# DIOT_EEM_Adapter.net
KiCad netlist of a schematic drawn in Altium Designer
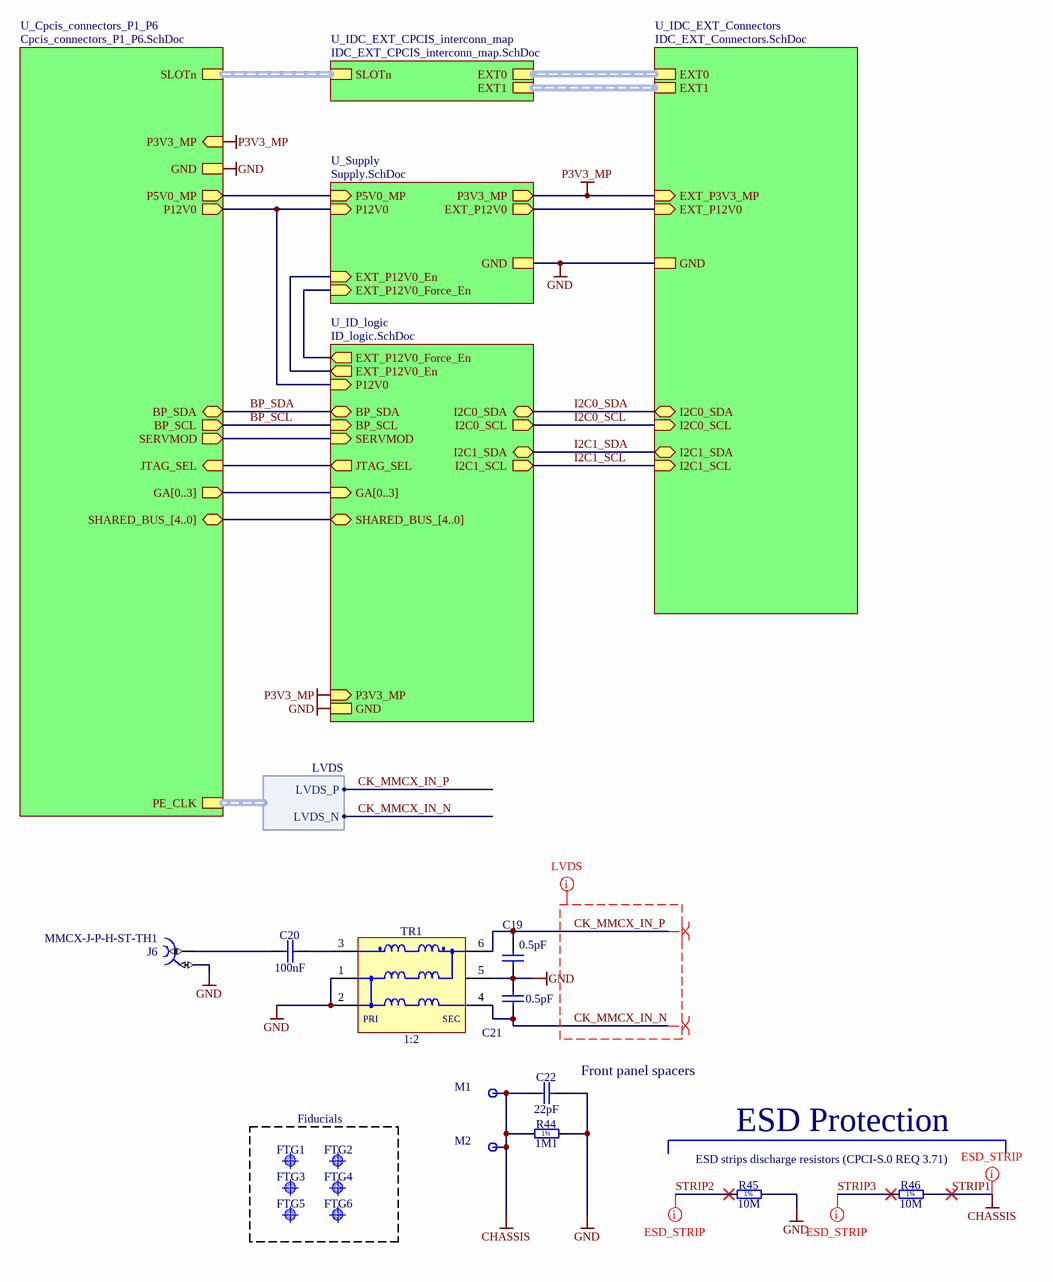
[diagram p0: DIOT_EEM_Adapter.SchDoc]

(export (version "E")
  (design (tool "Eeschema 10.0.6"))
  (components
    (comp (ref "C19")
      (value "0.5pF")
      (footprint "CAPC1005X50N")
      (description "Non-polarised capacitor")
      (fields
        (field (name "PART NUMBER") "CC0402_0.5PF_25V_0.05PF_AVX_04023J0R5ABSTR")
        (field (name "VOLTAGE") "25V")
        (field (name "AUTHOR") "CERN DEM JLC")
      )
      (libsource (lib "Capacitors") (part "Capacitor - non polarized"))
    )
    (comp (ref "C20")
      (value "100nF")
      (footprint "CAPC1005X55N")
      (description "Non-polarised capacitor")
      (fields
        (field (name "PART NUMBER") "CC0402_100NF_16V_10%_X7R")
        (field (name "VOLTAGE") "16V")
        (field (name "AUTHOR") "CERN DEM JLC")
      )
      (libsource (lib "Capacitors") (part "Capacitor - non polarized"))
    )
    (comp (ref "C21")
      (value "0.5pF")
      (footprint "CAPC1005X50N")
      (description "Non-polarised capacitor")
      (fields
        (field (name "PART NUMBER") "CC0402_0.5PF_25V_0.05PF_AVX_04023J0R5ABSTR")
        (field (name "VOLTAGE") "25V")
        (field (name "AUTHOR") "CERN DEM JLC")
      )
      (libsource (lib "Capacitors") (part "Capacitor - non polarized"))
    )
    (comp (ref "C22")
      (value "22pF")
      (footprint "CAPC1005X55N")
      (description "Non-polarised capacitor")
      (fields
        (field (name "PART NUMBER") "CC0402_22PF_50V_5%_C0G")
        (field (name "VOLTAGE") "50V")
        (field (name "AUTHOR") "CERN DEM JLC")
      )
      (libsource (lib "Capacitors") (part "Capacitor - non polarized"))
    )
    (comp (ref "FTG1")
      (value "Use only in PCB")
      (footprint "FIDUCIAL_TOP_S100-200")
      (description "Fiducial Target")
      (fields (field (name "PART NUMBER") "FIDUCIAL_TARGET_S100-200") (field (name "AUTHOR") "CERN DEM JLC"))
      (libsource (lib "Eletro-mechanical") (part "Fiducial Target"))
    )
    (comp (ref "FTG2")
      (value "Use only in PCB")
      (footprint "FIDUCIAL_TOP_S100-200")
      (description "Fiducial Target")
      (fields (field (name "PART NUMBER") "FIDUCIAL_TARGET_S100-200") (field (name "AUTHOR") "CERN DEM JLC"))
      (libsource (lib "Eletro-mechanical") (part "Fiducial Target"))
    )
    (comp (ref "FTG3")
      (value "Use only in PCB")
      (footprint "FIDUCIAL_TOP_S100-200")
      (description "Fiducial Target")
      (fields (field (name "PART NUMBER") "FIDUCIAL_TARGET_S100-200") (field (name "AUTHOR") "CERN DEM JLC"))
      (libsource (lib "Eletro-mechanical") (part "Fiducial Target"))
    )
    (comp (ref "FTG4")
      (value "Use only in PCB")
      (footprint "FIDUCIAL_TOP_S100-200")
      (description "Fiducial Target")
      (fields (field (name "PART NUMBER") "FIDUCIAL_TARGET_S100-200") (field (name "AUTHOR") "CERN DEM JLC"))
      (libsource (lib "Eletro-mechanical") (part "Fiducial Target"))
    )
    (comp (ref "FTG5")
      (value "Use only in PCB")
      (footprint "FIDUCIAL_TOP_S100-200")
      (description "Fiducial Target")
      (fields (field (name "PART NUMBER") "FIDUCIAL_TARGET_S100-200") (field (name "AUTHOR") "CERN DEM JLC"))
      (libsource (lib "Eletro-mechanical") (part "Fiducial Target"))
    )
    (comp (ref "FTG6")
      (value "Use only in PCB")
      (footprint "FIDUCIAL_TOP_S100-200")
      (description "Fiducial Target")
      (fields (field (name "PART NUMBER") "FIDUCIAL_TARGET_S100-200") (field (name "AUTHOR") "CERN DEM JLC"))
      (libsource (lib "Eletro-mechanical") (part "Fiducial Target"))
    )
    (comp (ref "J6")
      (value "MMCX-J-P-H-ST-TH1")
      (footprint "SAMTEC_MMCX-J-P-H-ST-TH1")
      (fields
        (field (name "PART NUMBER") "SAMTEC_MMCX-J-P-H-ST-TH1")
        (field (name "MANUFACTURER") "SAMTEC")
        (field (name "AUTHOR") "CERN DEM JLC")
      )
      (libsource (lib "Connectors") (part "Coax_1Female_1Shield"))
    )
    (comp (ref "M1")
      (value "Plated Hole")
      (footprint "MTG300_600")
      (description "Single Terminal Socket")
      (fields (field (name "PART NUMBER") "PLATED_HOLE3.0_PAD6.0") (field (name "AUTHOR") "CERN DEM JLC"))
      (libsource (lib "Eletro-mechanical") (part "Single Terminal Socket"))
    )
    (comp (ref "M2")
      (value "Plated Hole")
      (footprint "MTG300_600")
      (description "Single Terminal Socket")
      (fields (field (name "PART NUMBER") "PLATED_HOLE3.0_PAD6.0") (field (name "AUTHOR") "CERN DEM JLC"))
      (libsource (lib "Eletro-mechanical") (part "Single Terminal Socket"))
    )
    (comp (ref "R44")
      (value "1M1")
      (footprint "RESC2012X60N")
      (description "Resistor - 1%")
      (fields
        (field (name "PART NUMBER") "R0805_1M1_1%_0.125W_100PPM")
        (field (name "POWER") "0.125W")
        (field (name "AUTHOR") "CERN DEM JLC")
      )
      (libsource (lib "Resistors") (part "Resistor - 1%"))
    )
    (comp (ref "R45")
      (value "10M")
      (footprint "RESC2113X55N")
      (description "Resistor - 1%")
      (fields
        (field (name "PART NUMBER") "R0805_10M_1%_0.125W_100PPM_VISHAY_CRCW e3")
        (field (name "POWER") "0.125W")
        (field (name "AUTHOR") "CERN DEM BC")
      )
      (libsource (lib "Resistors") (part "Resistor - 1%"))
    )
    (comp (ref "R46")
      (value "10M")
      (footprint "RESC2113X55N")
      (description "Resistor - 1%")
      (fields
        (field (name "PART NUMBER") "R0805_10M_1%_0.125W_100PPM_VISHAY_CRCW e3")
        (field (name "POWER") "0.125W")
        (field (name "AUTHOR") "CERN DEM BC")
      )
      (libsource (lib "Resistors") (part "Resistor - 1%"))
    )
    (comp (ref "TR1")
      (value "1:2")
      (footprint "XFMR_MINI-CIRCUITS_DB1627")
      (description "50 OHMS 10 to 4000 MHz RF Transformer")
      (fields
        (field (name "PART NUMBER") "XFMR_MINI-CIRCUITS_TCM2-43X+")
        (field (name "POWER") "0.4W")
        (field (name "AUTHOR") "CERN DEM BC")
      )
      (libsource (lib "Inductors & Transformers") (part "XFMR_MINI-CIRCUITS_TCM2-43X"))
    )
  )
  (nets
    (net (code "4") (name "/CK_MMCX_IN_N") (class "Default")
      (node (ref "C21") (pin "1") (pinfunction "1_1") (pintype "passive"))
      (node (ref "TR1") (pin "4") (pinfunction "S1_4") (pintype "passive"))
    )
    (net (code "5") (name "/CK_MMCX_IN_P") (class "Default")
      (node (ref "C19") (pin "2") (pinfunction "2_2") (pintype "passive"))
      (node (ref "TR1") (pin "6") (pinfunction "S1_6") (pintype "passive"))
    )
    (net (code "23") (name "/STRIP2") (class "Default")
      (node (ref "R45") (pin "1") (pinfunction "1_1") (pintype "passive+no_connect"))
    )
    (net (code "24") (name "/STRIP3") (class "Default")
      (node (ref "R46") (pin "1") (pinfunction "1_1") (pintype "passive+no_connect"))
    )
    (net (code "26") (name "CHASSIS") (class "Default")
      (node (ref "C22") (pin "1") (pinfunction "1_1") (pintype "passive"))
      (node (ref "M1") (pin "1") (pinfunction "1_1") (pintype "bidirectional"))
      (node (ref "M2") (pin "1") (pinfunction "1_1") (pintype "bidirectional"))
      (node (ref "R44") (pin "1") (pinfunction "1_1") (pintype "passive"))
      (node (ref "R46") (pin "2") (pinfunction "2_2") (pintype "passive"))
    )
    (net (code "27") (name "GND") (class "Default")
      (node (ref "C19") (pin "1") (pinfunction "1_1") (pintype "passive"))
      (node (ref "C21") (pin "2") (pinfunction "2_2") (pintype "passive"))
      (node (ref "C22") (pin "2") (pinfunction "2_2") (pintype "passive"))
      (node (ref "J6") (pin "2") (pinfunction "2_2") (pintype "bidirectional"))
      (node (ref "R44") (pin "2") (pinfunction "2_2") (pintype "passive"))
      (node (ref "R45") (pin "2") (pinfunction "2_2") (pintype "passive"))
      (node (ref "TR1") (pin "1") (pinfunction "P1_1") (pintype "passive"))
      (node (ref "TR1") (pin "2") (pinfunction "P1_2") (pintype "passive"))
      (node (ref "TR1") (pin "5") (pinfunction "NC_5") (pintype "passive"))
    )
    (net (code "28") (name "Net-(C20-Pad1)") (class "Default")
      (node (ref "C20") (pin "1") (pinfunction "1_1") (pintype "passive"))
      (node (ref "J6") (pin "1") (pinfunction "1_1") (pintype "bidirectional"))
    )
    (net (code "29") (name "Net-(C20-Pad2)") (class "Default")
      (node (ref "C20") (pin "2") (pinfunction "2_2") (pintype "passive"))
      (node (ref "TR1") (pin "3") (pinfunction "P1_3") (pintype "passive"))
    )
  )
)
